# Watch2.net
KiCad netlist of a schematic drawn in EAGLE
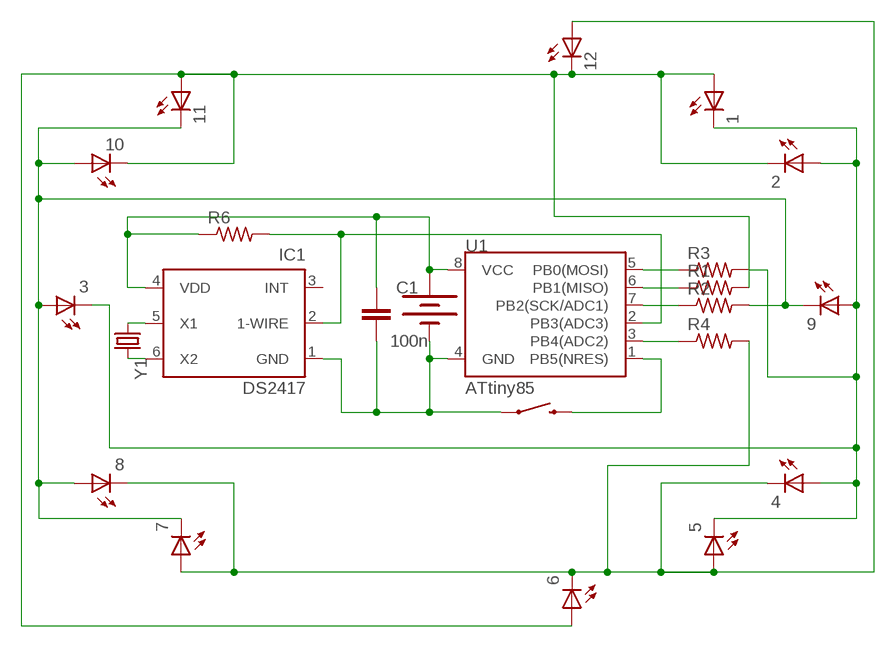
[diagram p0: schematic, sheet 1]

(export (version "E")
  (design (tool "Eeschema 10.0.6"))
  (components
    (comp (ref "1")
      (value "LEDCHIPLED_0805")
      (footprint "eagle-import:CHIPLED_0805")
      (libsource (lib "eagle-import") (part "LEDCHIPLED_0805"))
    )
    (comp (ref "2")
      (value "LEDCHIPLED_0805")
      (footprint "eagle-import:CHIPLED_0805")
      (libsource (lib "eagle-import") (part "LEDCHIPLED_0805"))
    )
    (comp (ref "3")
      (value "LEDCHIPLED_0805")
      (footprint "eagle-import:CHIPLED_0805")
      (libsource (lib "eagle-import") (part "LEDCHIPLED_0805"))
    )
    (comp (ref "4")
      (value "LEDCHIPLED_0805")
      (footprint "eagle-import:CHIPLED_0805")
      (libsource (lib "eagle-import") (part "LEDCHIPLED_0805"))
    )
    (comp (ref "5")
      (value "LEDCHIPLED_0805")
      (footprint "eagle-import:CHIPLED_0805")
      (libsource (lib "eagle-import") (part "LEDCHIPLED_0805"))
    )
    (comp (ref "6")
      (value "LEDCHIPLED_0805")
      (footprint "eagle-import:CHIPLED_0805")
      (libsource (lib "eagle-import") (part "LEDCHIPLED_0805"))
    )
    (comp (ref "7")
      (value "LEDCHIPLED_0805")
      (footprint "eagle-import:CHIPLED_0805")
      (libsource (lib "eagle-import") (part "LEDCHIPLED_0805"))
    )
    (comp (ref "8")
      (value "LEDCHIPLED_0805")
      (footprint "eagle-import:CHIPLED_0805")
      (libsource (lib "eagle-import") (part "LEDCHIPLED_0805"))
    )
    (comp (ref "9")
      (value "LEDCHIPLED_0805")
      (footprint "eagle-import:CHIPLED_0805")
      (libsource (lib "eagle-import") (part "LEDCHIPLED_0805"))
    )
    (comp (ref "10")
      (value "LEDCHIPLED_0805")
      (footprint "eagle-import:CHIPLED_0805")
      (libsource (lib "eagle-import") (part "LEDCHIPLED_0805"))
    )
    (comp (ref "11")
      (value "LEDCHIPLED_0805")
      (footprint "eagle-import:CHIPLED_0805")
      (libsource (lib "eagle-import") (part "LEDCHIPLED_0805"))
    )
    (comp (ref "12")
      (value "LEDCHIPLED_0805")
      (footprint "eagle-import:CHIPLED_0805")
      (libsource (lib "eagle-import") (part "LEDCHIPLED_0805"))
    )
    (comp (ref "BAT1")
      (value "20mm coincell")
      (footprint "eagle-import:BATTCON_20MM_4LEGS")
      (libsource (lib "eagle-import") (part "BATTERY20MM_4LEGS"))
    )
    (comp (ref "C1")
      (value "100n")
      (footprint "eagle-import:0603-CAP")
      (libsource (lib "eagle-import") (part "CAP0603-CAP"))
    )
    (comp (ref "IC1")
      (value "DS2417")
      (footprint "eagle-import:TSOC6")
      (libsource (lib "eagle-import") (part "DS2417P"))
    )
    (comp (ref "R1")
      (value "R-US_M0805")
      (footprint "eagle-import:M0805")
      (libsource (lib "eagle-import") (part "R-US_M0805"))
    )
    (comp (ref "R2")
      (value "R-US_M0805")
      (footprint "eagle-import:M0805")
      (libsource (lib "eagle-import") (part "R-US_M0805"))
    )
    (comp (ref "R3")
      (value "R-US_M0805")
      (footprint "eagle-import:M0805")
      (libsource (lib "eagle-import") (part "R-US_M0805"))
    )
    (comp (ref "R4")
      (value "R-US_M0805")
      (footprint "eagle-import:M0805")
      (libsource (lib "eagle-import") (part "R-US_M0805"))
    )
    (comp (ref "R6")
      (value "R-US_M0805")
      (footprint "eagle-import:M0805")
      (libsource (lib "eagle-import") (part "R-US_M0805"))
    )
    (comp (ref "S2")
      (value "SWITCH-MOMENTARY-2SMD")
      (footprint "eagle-import:TACTILE-SWITCH-SMD")
      (libsource (lib "eagle-import") (part "SWITCH-MOMENTARY-2SMD"))
    )
    (comp (ref "U1")
      (value "ATtiny85")
      (footprint "eagle-import:SO08-EIAJ")
      (libsource (lib "eagle-import") (part "ATTINY45TINY45-20-SMT"))
    )
    (comp (ref "Y1")
      (value "CRYSTAL32-SMD-MELF")
      (footprint "eagle-import:CRYSTAL-32KHZ-SMD-MELF")
      (libsource (lib "eagle-import") (part "CRYSTAL32-SMD-MELF"))
    )
  )
  (nets
    (net (code "1") (name "/INT") (class "Default")
      (node (ref "IC1") (pin "3") (pinfunction "INT_3") (pintype "power_in"))
    )
    (net (code "2") (name "Net-(1-PadA)") (class "Default")
      (node (ref "1") (pin "A") (pinfunction "A_A") (pintype "passive"))
      (node (ref "10") (pin "C") (pinfunction "C_C") (pintype "passive"))
      (node (ref "11") (pin "A") (pinfunction "A_A") (pintype "passive"))
      (node (ref "12") (pin "C") (pinfunction "C_C") (pintype "passive"))
      (node (ref "2") (pin "C") (pinfunction "C_C") (pintype "passive"))
      (node (ref "6") (pin "A") (pinfunction "A_A") (pintype "passive"))
      (node (ref "R1") (pin "2") (pinfunction "2_2") (pintype "passive"))
    )
    (net (code "3") (name "Net-(1-PadC)") (class "Default")
      (node (ref "1") (pin "C") (pinfunction "C_C") (pintype "passive"))
      (node (ref "2") (pin "A") (pinfunction "A_A") (pintype "passive"))
      (node (ref "3") (pin "C") (pinfunction "C_C") (pintype "passive"))
      (node (ref "4") (pin "A") (pinfunction "A_A") (pintype "passive"))
      (node (ref "5") (pin "C") (pinfunction "C_C") (pintype "passive"))
      (node (ref "9") (pin "A") (pinfunction "A_A") (pintype "passive"))
      (node (ref "R3") (pin "2") (pinfunction "2_2") (pintype "passive"))
    )
    (net (code "4") (name "Net-(10-PadA)") (class "Default")
      (node (ref "10") (pin "A") (pinfunction "A_A") (pintype "passive"))
      (node (ref "11") (pin "C") (pinfunction "C_C") (pintype "passive"))
      (node (ref "3") (pin "A") (pinfunction "A_A") (pintype "passive"))
      (node (ref "7") (pin "C") (pinfunction "C_C") (pintype "passive"))
      (node (ref "8") (pin "A") (pinfunction "A_A") (pintype "passive"))
      (node (ref "9") (pin "C") (pinfunction "C_C") (pintype "passive"))
      (node (ref "R2") (pin "2") (pinfunction "2_2") (pintype "passive"))
    )
    (net (code "5") (name "Net-(12-PadA)") (class "Default")
      (node (ref "12") (pin "A") (pinfunction "A_A") (pintype "passive"))
      (node (ref "4") (pin "C") (pinfunction "C_C") (pintype "passive"))
      (node (ref "5") (pin "A") (pinfunction "A_A") (pintype "passive"))
      (node (ref "6") (pin "C") (pinfunction "C_C") (pintype "passive"))
      (node (ref "7") (pin "A") (pinfunction "A_A") (pintype "passive"))
      (node (ref "8") (pin "C") (pinfunction "C_C") (pintype "passive"))
      (node (ref "R4") (pin "2") (pinfunction "2_2") (pintype "passive"))
    )
    (net (code "6") (name "Net-(BAT1--)") (class "Default")
      (node (ref "BAT1") (pin "NEGATIVE") (pinfunction "-_NEGATIVE") (pintype "power_in"))
      (node (ref "C1") (pin "2") (pinfunction "2_2") (pintype "passive"))
      (node (ref "IC1") (pin "1") (pinfunction "GND_1") (pintype "power_in"))
      (node (ref "S2") (pin "1") (pinfunction "1_1") (pintype "passive"))
      (node (ref "U1") (pin "4") (pinfunction "GND_4") (pintype "bidirectional"))
    )
    (net (code "7") (name "Net-(IC1-1-WIRE)") (class "Default")
      (node (ref "IC1") (pin "2") (pinfunction "1-WIRE_2") (pintype "bidirectional"))
      (node (ref "R6") (pin "2") (pinfunction "2_2") (pintype "passive"))
      (node (ref "U1") (pin "2") (pinfunction "PB3(ADC3)_2") (pintype "bidirectional"))
    )
    (net (code "8") (name "Net-(IC1-VDD)") (class "Default")
      (node (ref "BAT1") (pin "POSITIVE@1") (pinfunction "+_POSITIVE@1") (pintype "power_in"))
      (node (ref "BAT1") (pin "POSITIVE@2") (pinfunction "+_POSITIVE@2") (pintype "power_in"))
      (node (ref "BAT1") (pin "POSITIVE@3") (pinfunction "+_POSITIVE@3") (pintype "power_in"))
      (node (ref "BAT1") (pin "POSITIVE@4") (pinfunction "+_POSITIVE@4") (pintype "power_in"))
      (node (ref "C1") (pin "1") (pinfunction "1_1") (pintype "passive"))
      (node (ref "IC1") (pin "4") (pinfunction "VDD_4") (pintype "passive"))
      (node (ref "R6") (pin "1") (pinfunction "1_1") (pintype "passive"))
      (node (ref "U1") (pin "8") (pinfunction "VCC_8") (pintype "bidirectional"))
    )
    (net (code "9") (name "Net-(IC1-X1)") (class "Default")
      (node (ref "IC1") (pin "5") (pinfunction "X1_5") (pintype "passive"))
      (node (ref "Y1") (pin "X1") (pinfunction "1_X1") (pintype "passive"))
    )
    (net (code "10") (name "Net-(IC1-X2)") (class "Default")
      (node (ref "IC1") (pin "6") (pinfunction "X2_6") (pintype "passive"))
      (node (ref "Y1") (pin "X2") (pinfunction "2_X2") (pintype "passive"))
    )
    (net (code "11") (name "Net-(S2-2)") (class "Default")
      (node (ref "S2") (pin "3") (pinfunction "2_3") (pintype "passive"))
      (node (ref "U1") (pin "1") (pinfunction "PB5(NRES)_1") (pintype "bidirectional"))
    )
    (net (code "12") (name "Net-(U1-PB0(MOSI))") (class "Default")
      (node (ref "R3") (pin "1") (pinfunction "1_1") (pintype "passive"))
      (node (ref "U1") (pin "5") (pinfunction "PB0(MOSI)_5") (pintype "bidirectional"))
    )
    (net (code "13") (name "Net-(U1-PB1(MISO))") (class "Default")
      (node (ref "R1") (pin "1") (pinfunction "1_1") (pintype "passive"))
      (node (ref "U1") (pin "6") (pinfunction "PB1(MISO)_6") (pintype "bidirectional"))
    )
    (net (code "14") (name "Net-(U1-PB2(SCK{slash}ADC1))") (class "Default")
      (node (ref "R2") (pin "1") (pinfunction "1_1") (pintype "passive"))
      (node (ref "U1") (pin "7") (pinfunction "PB2(SCK/ADC1)_7") (pintype "bidirectional"))
    )
    (net (code "15") (name "Net-(U1-PB4(ADC2))") (class "Default")
      (node (ref "R4") (pin "1") (pinfunction "1_1") (pintype "passive"))
      (node (ref "U1") (pin "3") (pinfunction "PB4(ADC2)_3") (pintype "bidirectional"))
    )
  )
)
